# AirPurity.net
KiCad netlist of a schematic drawn in Altium Designer
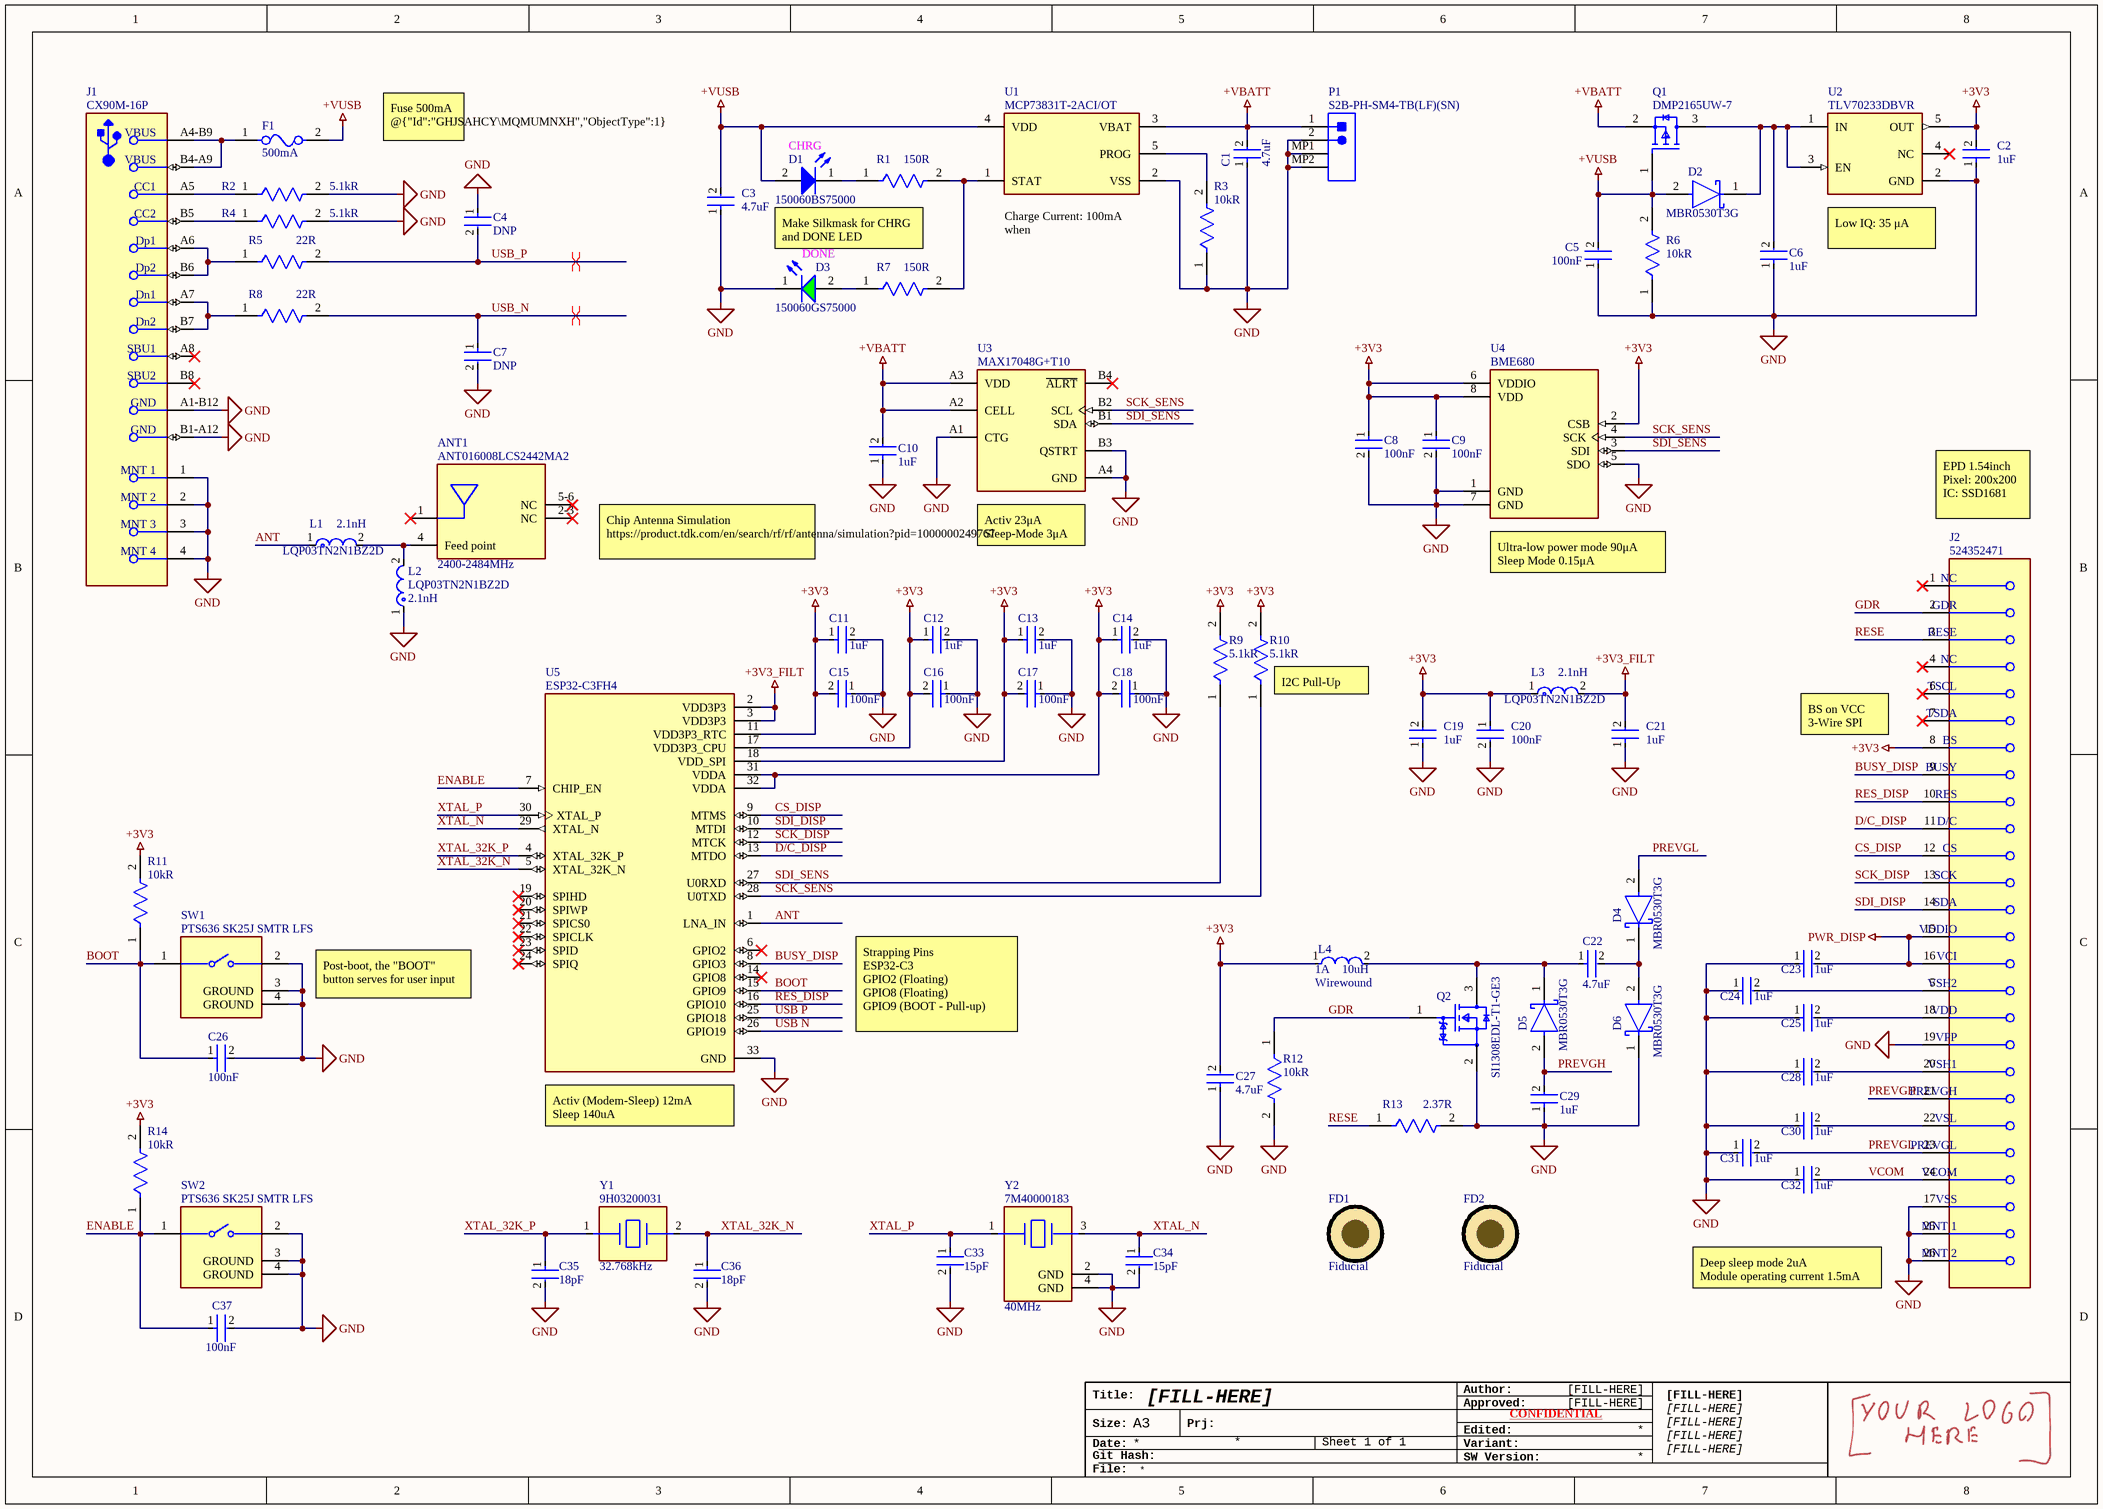
[diagram p0: AirPurity.SchDoc]

(export (version "E")
  (design (tool "Eeschema 10.0.6"))
  (components
    (comp (ref "ANT1")
      (value "ANT016008LCS2442MA2")
      (footprint "FP-ANT016008LCS2442MA2-0")
      (description "RF ANT 2.4GHZ CHIP SOLDER SMD")
      (fields
        (field (name "MANUFACTURER") "TDK Corporation")
        (field (name "OCTOPART") "https://octopart.com/ant016008lcs2442ma2-tdk-48293801")
        (field (name "BANDWIDTH") "2400-2484MHz")
      )
      (libsource (lib "Altium Content Vault") (part "6c2c938d67d116ee9870b08397b3bde"))
    )
    (comp (ref "C1")
      (value "GRM155R61E475ME15D")
      (footprint "FP-GRM155-0_2-MFG")
      (fields (field (name "CAPACITANCE") "4.7uF"))
      (libsource (lib "Altium Content Vault") (part "02cd4be3c70576c341d710602a673aa"))
    )
    (comp (ref "C2")
      (value "GRM155R61E105KA12D")
      (footprint "FP-GRM155-0_1-MFG")
      (description "CERAMIC CAP, MLCC 1UF 50VDC X5R")
      (fields (field (name "CAPACITANCE") "1uF"))
      (libsource (lib "Altium Content Vault") (part "b4654b650e69147ec39a6b967a45e02"))
    )
    (comp (ref "C3")
      (value "GRM155R61E475ME15D")
      (footprint "FP-GRM155-0_2-MFG")
      (fields (field (name "CAPACITANCE") "4.7uF"))
      (libsource (lib "Altium Content Vault") (part "02cd4be3c70576c341d710602a673aa"))
    )
    (comp (ref "C4")
      (value "GRM033R61A104KE15D")
      (footprint "FP-GRM033-0_03-MFG")
      (description "Chip Multilayer Ceramic Capacitors for General Purpose, 0201, 0.10uF, X5R, 15%, 10%, 10V")
      (fields
        (field (name "TOLERANCE") "10%")
        (field (name "CAPACITANCE") "DNP")
        (field (name "VOLTAGE") "10V")
      )
      (libsource (lib "Altium Content Vault") (part "b4654b650e69147ec39a6b967a45e02"))
    )
    (comp (ref "C5")
      (value "GRM033R61A104KE15D")
      (footprint "FP-GRM033-0_03-MFG")
      (description "Chip Multilayer Ceramic Capacitors for General Purpose, 0201, 0.10uF, X5R, 15%, 10%, 10V")
      (fields
        (field (name "TOLERANCE") "10%")
        (field (name "CAPACITANCE") "100nF")
        (field (name "VOLTAGE") "10V")
      )
      (libsource (lib "Altium Content Vault") (part "b4654b650e69147ec39a6b967a45e02"))
    )
    (comp (ref "C6")
      (value "GRM155R61E105KA12D")
      (footprint "FP-GRM155-0_1-MFG")
      (description "CERAMIC CAP, MLCC 1UF 50VDC X5R")
      (fields (field (name "CAPACITANCE") "1uF"))
      (libsource (lib "Altium Content Vault") (part "b4654b650e69147ec39a6b967a45e02"))
    )
    (comp (ref "C7")
      (value "GRM033R61A104KE15D")
      (footprint "FP-GRM033-0_03-MFG")
      (description "Chip Multilayer Ceramic Capacitors for General Purpose, 0201, 0.10uF, X5R, 15%, 10%, 10V")
      (fields
        (field (name "TOLERANCE") "10%")
        (field (name "CAPACITANCE") "DNP")
        (field (name "VOLTAGE") "10V")
      )
      (libsource (lib "Altium Content Vault") (part "b4654b650e69147ec39a6b967a45e02"))
    )
    (comp (ref "C8")
      (value "GRM033R61A104KE15D")
      (footprint "FP-GRM033-0_03-MFG")
      (description "Chip Multilayer Ceramic Capacitors for General Purpose, 0201, 0.10uF, X5R, 15%, 10%, 10V")
      (fields
        (field (name "TOLERANCE") "10%")
        (field (name "CAPACITANCE") "100nF")
        (field (name "VOLTAGE") "10V")
      )
      (libsource (lib "Altium Content Vault") (part "b4654b650e69147ec39a6b967a45e02"))
    )
    (comp (ref "C9")
      (value "GRM033R61A104KE15D")
      (footprint "FP-GRM033-0_03-MFG")
      (description "Chip Multilayer Ceramic Capacitors for General Purpose, 0201, 0.10uF, X5R, 15%, 10%, 10V")
      (fields
        (field (name "TOLERANCE") "10%")
        (field (name "CAPACITANCE") "100nF")
        (field (name "VOLTAGE") "10V")
      )
      (libsource (lib "Altium Content Vault") (part "b4654b650e69147ec39a6b967a45e02"))
    )
    (comp (ref "C10")
      (value "GRM155R61E105KA12D")
      (footprint "FP-GRM155-0_1-MFG")
      (description "CERAMIC CAP, MLCC 1UF 50VDC X5R")
      (fields (field (name "CAPACITANCE") "1uF"))
      (libsource (lib "Altium Content Vault") (part "b4654b650e69147ec39a6b967a45e02"))
    )
    (comp (ref "C11")
      (value "GRM155R61E105KA12D")
      (footprint "FP-GRM155-0_1-MFG")
      (description "CERAMIC CAP, MLCC 1UF 50VDC X5R")
      (fields (field (name "CAPACITANCE") "1uF"))
      (libsource (lib "Altium Content Vault") (part "b4654b650e69147ec39a6b967a45e02"))
    )
    (comp (ref "C12")
      (value "GRM155R61E105KA12D")
      (footprint "FP-GRM155-0_1-MFG")
      (description "CERAMIC CAP, MLCC 1UF 50VDC X5R")
      (fields (field (name "CAPACITANCE") "1uF"))
      (libsource (lib "Altium Content Vault") (part "b4654b650e69147ec39a6b967a45e02"))
    )
    (comp (ref "C13")
      (value "GRM155R61E105KA12D")
      (footprint "FP-GRM155-0_1-MFG")
      (description "CERAMIC CAP, MLCC 1UF 50VDC X5R")
      (fields (field (name "CAPACITANCE") "1uF"))
      (libsource (lib "Altium Content Vault") (part "b4654b650e69147ec39a6b967a45e02"))
    )
    (comp (ref "C14")
      (value "GRM155R61E105KA12D")
      (footprint "FP-GRM155-0_1-MFG")
      (description "CERAMIC CAP, MLCC 1UF 50VDC X5R")
      (fields (field (name "CAPACITANCE") "1uF"))
      (libsource (lib "Altium Content Vault") (part "b4654b650e69147ec39a6b967a45e02"))
    )
    (comp (ref "C15")
      (value "GRM033R61A104KE15D")
      (footprint "FP-GRM033-0_03-MFG")
      (description "Chip Multilayer Ceramic Capacitors for General Purpose, 0201, 0.10uF, X5R, 15%, 10%, 10V")
      (fields
        (field (name "TOLERANCE") "10%")
        (field (name "CAPACITANCE") "100nF")
        (field (name "VOLTAGE") "10V")
      )
      (libsource (lib "Altium Content Vault") (part "b4654b650e69147ec39a6b967a45e02"))
    )
    (comp (ref "C16")
      (value "GRM033R61A104KE15D")
      (footprint "FP-GRM033-0_03-MFG")
      (description "Chip Multilayer Ceramic Capacitors for General Purpose, 0201, 0.10uF, X5R, 15%, 10%, 10V")
      (fields
        (field (name "TOLERANCE") "10%")
        (field (name "CAPACITANCE") "100nF")
        (field (name "VOLTAGE") "10V")
      )
      (libsource (lib "Altium Content Vault") (part "b4654b650e69147ec39a6b967a45e02"))
    )
    (comp (ref "C17")
      (value "GRM033R61A104KE15D")
      (footprint "FP-GRM033-0_03-MFG")
      (description "Chip Multilayer Ceramic Capacitors for General Purpose, 0201, 0.10uF, X5R, 15%, 10%, 10V")
      (fields
        (field (name "TOLERANCE") "10%")
        (field (name "CAPACITANCE") "100nF")
        (field (name "VOLTAGE") "10V")
      )
      (libsource (lib "Altium Content Vault") (part "b4654b650e69147ec39a6b967a45e02"))
    )
    (comp (ref "C18")
      (value "GRM033R61A104KE15D")
      (footprint "FP-GRM033-0_03-MFG")
      (description "Chip Multilayer Ceramic Capacitors for General Purpose, 0201, 0.10uF, X5R, 15%, 10%, 10V")
      (fields
        (field (name "TOLERANCE") "10%")
        (field (name "CAPACITANCE") "100nF")
        (field (name "VOLTAGE") "10V")
      )
      (libsource (lib "Altium Content Vault") (part "b4654b650e69147ec39a6b967a45e02"))
    )
    (comp (ref "C19")
      (value "GRM155R61E105KA12D")
      (footprint "FP-GRM155-0_1-MFG")
      (description "CERAMIC CAP, MLCC 1UF 50VDC X5R")
      (fields (field (name "CAPACITANCE") "1uF"))
      (libsource (lib "Altium Content Vault") (part "b4654b650e69147ec39a6b967a45e02"))
    )
    (comp (ref "C20")
      (value "GRM033R61A104KE15D")
      (footprint "FP-GRM033-0_03-MFG")
      (description "Chip Multilayer Ceramic Capacitors for General Purpose, 0201, 0.10uF, X5R, 15%, 10%, 10V")
      (fields
        (field (name "TOLERANCE") "10%")
        (field (name "CAPACITANCE") "100nF")
        (field (name "VOLTAGE") "10V")
      )
      (libsource (lib "Altium Content Vault") (part "b4654b650e69147ec39a6b967a45e02"))
    )
    (comp (ref "C21")
      (value "GRM155R61E105KA12D")
      (footprint "FP-GRM155-0_1-MFG")
      (description "CERAMIC CAP, MLCC 1UF 50VDC X5R")
      (fields (field (name "CAPACITANCE") "1uF"))
      (libsource (lib "Altium Content Vault") (part "b4654b650e69147ec39a6b967a45e02"))
    )
    (comp (ref "C22")
      (value "GRM155R61E475ME15D")
      (footprint "FP-GRM155-0_2-MFG")
      (fields (field (name "CAPACITANCE") "4.7uF"))
      (libsource (lib "Altium Content Vault") (part "02cd4be3c70576c341d710602a673aa"))
    )
    (comp (ref "C23")
      (value "GRM155R61E105KA12D")
      (footprint "FP-GRM155-0_1-MFG")
      (description "CERAMIC CAP, MLCC 1UF 50VDC X5R")
      (fields (field (name "CAPACITANCE") "1uF"))
      (libsource (lib "Altium Content Vault") (part "b4654b650e69147ec39a6b967a45e02"))
    )
    (comp (ref "C24")
      (value "GRM155R61E105KA12D")
      (footprint "FP-GRM155-0_1-MFG")
      (description "CERAMIC CAP, MLCC 1UF 50VDC X5R")
      (fields (field (name "CAPACITANCE") "1uF"))
      (libsource (lib "Altium Content Vault") (part "b4654b650e69147ec39a6b967a45e02"))
    )
    (comp (ref "C25")
      (value "GRM155R61E105KA12D")
      (footprint "FP-GRM155-0_1-MFG")
      (description "CERAMIC CAP, MLCC 1UF 50VDC X5R")
      (fields (field (name "CAPACITANCE") "1uF"))
      (libsource (lib "Altium Content Vault") (part "b4654b650e69147ec39a6b967a45e02"))
    )
    (comp (ref "C26")
      (value "GRM033R61A104KE15D")
      (footprint "FP-GRM033-0_03-MFG")
      (description "Chip Multilayer Ceramic Capacitors for General Purpose, 0201, 0.10uF, X5R, 15%, 10%, 10V")
      (fields
        (field (name "TOLERANCE") "10%")
        (field (name "CAPACITANCE") "100nF")
        (field (name "VOLTAGE") "10V")
      )
      (libsource (lib "Altium Content Vault") (part "b4654b650e69147ec39a6b967a45e02"))
    )
    (comp (ref "C27")
      (value "GRM155R61E475ME15D")
      (footprint "FP-GRM155-0_2-MFG")
      (fields (field (name "CAPACITANCE") "4.7uF"))
      (libsource (lib "Altium Content Vault") (part "02cd4be3c70576c341d710602a673aa"))
    )
    (comp (ref "C28")
      (value "GRM155R61E105KA12D")
      (footprint "FP-GRM155-0_1-MFG")
      (description "CERAMIC CAP, MLCC 1UF 50VDC X5R")
      (fields (field (name "CAPACITANCE") "1uF"))
      (libsource (lib "Altium Content Vault") (part "b4654b650e69147ec39a6b967a45e02"))
    )
    (comp (ref "C29")
      (value "GRM155R61E105KA12D")
      (footprint "FP-GRM155-0_1-MFG")
      (description "CERAMIC CAP, MLCC 1UF 50VDC X5R")
      (fields (field (name "CAPACITANCE") "1uF"))
      (libsource (lib "Altium Content Vault") (part "b4654b650e69147ec39a6b967a45e02"))
    )
    (comp (ref "C30")
      (value "GRM155R61E105KA12D")
      (footprint "FP-GRM155-0_1-MFG")
      (description "CERAMIC CAP, MLCC 1UF 50VDC X5R")
      (fields (field (name "CAPACITANCE") "1uF"))
      (libsource (lib "Altium Content Vault") (part "b4654b650e69147ec39a6b967a45e02"))
    )
    (comp (ref "C31")
      (value "GRM155R61E105KA12D")
      (footprint "FP-GRM155-0_1-MFG")
      (description "CERAMIC CAP, MLCC 1UF 50VDC X5R")
      (fields (field (name "CAPACITANCE") "1uF"))
      (libsource (lib "Altium Content Vault") (part "b4654b650e69147ec39a6b967a45e02"))
    )
    (comp (ref "C32")
      (value "GRM155R61E105KA12D")
      (footprint "FP-GRM155-0_1-MFG")
      (description "CERAMIC CAP, MLCC 1UF 50VDC X5R")
      (fields (field (name "CAPACITANCE") "1uF"))
      (libsource (lib "Altium Content Vault") (part "b4654b650e69147ec39a6b967a45e02"))
    )
    (comp (ref "C33")
      (value "GRM0335C1H150FA01D")
      (footprint "FP-GRM033-0_03-IPC_B")
      (description "Chip Multilayer Ceramic Capacitors for General Purpose, 0201, 15pF, C0G, 30ppm/°C, 1%, 50V")
      (fields (field (name "CAPACITANCE") "15pF"))
      (libsource (lib "Altium Content Vault") (part "b4654b650e69147ec39a6b967a45e02"))
    )
    (comp (ref "C34")
      (value "GRM0335C1H150FA01D")
      (footprint "FP-GRM033-0_03-IPC_B")
      (description "Chip Multilayer Ceramic Capacitors for General Purpose, 0201, 15pF, C0G, 30ppm/°C, 1%, 50V")
      (fields (field (name "CAPACITANCE") "15pF"))
      (libsource (lib "Altium Content Vault") (part "b4654b650e69147ec39a6b967a45e02"))
    )
    (comp (ref "C35")
      (value "GRM0335C1H180FA01D")
      (footprint "FP-GRM033-0_03-MFG")
      (description "Chip Multilayer Ceramic Capacitors for General Purpose, 0201, 18pF, C0G, 30ppm/°C, 1%, 50V")
      (fields (field (name "CAPACITANCE") "18pF"))
      (libsource (lib "Altium Content Vault") (part "b4654b650e69147ec39a6b967a45e02"))
    )
    (comp (ref "C36")
      (value "GRM0335C1H180FA01D")
      (footprint "FP-GRM033-0_03-MFG")
      (description "Chip Multilayer Ceramic Capacitors for General Purpose, 0201, 18pF, C0G, 30ppm/°C, 1%, 50V")
      (fields (field (name "CAPACITANCE") "18pF"))
      (libsource (lib "Altium Content Vault") (part "b4654b650e69147ec39a6b967a45e02"))
    )
    (comp (ref "C37")
      (value "GRM033R61A104KE15D")
      (footprint "FP-GRM033-0_03-MFG")
      (description "Chip Multilayer Ceramic Capacitors for General Purpose, 0201, 0.10uF, X5R, 15%, 10%, 10V")
      (fields
        (field (name "TOLERANCE") "10%")
        (field (name "CAPACITANCE") "100nF")
        (field (name "VOLTAGE") "10V")
      )
      (libsource (lib "Altium Content Vault") (part "b4654b650e69147ec39a6b967a45e02"))
    )
    (comp (ref "D1")
      (value "150060BS75000")
      (footprint "WL-SMCW_0603_150060xx75000")
      (libsource (lib "Altium Content Vault") (part "LED_Blue_2A-1K"))
    )
    (comp (ref "D2")
      (value "MBR0530T3G")
      (footprint "FP-425-04-MFG")
      (description "DIODE SCHOTTKY 30V 500MA SOD123")
      (libsource (lib "Altium Content Vault") (part "1d6ec82d83fb6aee721767c19dac4b9"))
    )
    (comp (ref "D3")
      (value "150060GS75000")
      (footprint "WL-SMCW_0603_150060xx75000")
      (libsource (lib "Altium Content Vault") (part "LED_Green_2A-1K"))
    )
    (comp (ref "D4")
      (value "MBR0530T3G")
      (footprint "FP-425-04-MFG")
      (description "DIODE SCHOTTKY 30V 500MA SOD123")
      (libsource (lib "Altium Content Vault") (part "1d6ec82d83fb6aee721767c19dac4b9"))
    )
    (comp (ref "D5")
      (value "MBR0530T3G")
      (footprint "FP-425-04-MFG")
      (description "DIODE SCHOTTKY 30V 500MA SOD123")
      (libsource (lib "Altium Content Vault") (part "1d6ec82d83fb6aee721767c19dac4b9"))
    )
    (comp (ref "D6")
      (value "MBR0530T3G")
      (footprint "FP-425-04-MFG")
      (description "DIODE SCHOTTKY 30V 500MA SOD123")
      (libsource (lib "Altium Content Vault") (part "1d6ec82d83fb6aee721767c19dac4b9"))
    )
    (comp (ref "F1")
      (value "0466.500NRHF")
      (footprint "FP-0466-MFG")
      (description "FUSE BOARD MOUNT 500MA 63VAC/VDC")
      (fields (field (name "CURRENT RATING") "500mA"))
      (libsource (lib "Altium Content Vault") (part "5bcf9b9f640e542cf0359d10258e979"))
    )
    (comp (ref "FD1")
      (value "Fiducial")
      (footprint "FIDUCIAL-1MM")
      (libsource (lib "Library") (part "Fiducial"))
    )
    (comp (ref "FD2")
      (value "Fiducial")
      (footprint "FIDUCIAL-1MM")
      (libsource (lib "Library") (part "Fiducial"))
    )
    (comp (ref "J1")
      (value "CX90M-16P")
      (footprint "FP-USB4105-GF-A-MFG")
      (description "CONN RCPT USB2.0 TYPEC 5A")
      (fields (field (name "MANUFACTURER PART NUMBER") "USB4105-GF-A") (field (name "MANUFACTURER") "GCT"))
      (libsource (lib "Library") (part "CMP-245163-000001-1"))
    )
    (comp (ref "J2")
      (value "524352471")
      (footprint "FP-505110-2491-MFG")
      (description "CONN FFC/FPC BOTTOM 24P .5MM R/A")
      (libsource (lib "Library") (part "CMP-04775-000015-1"))
    )
    (comp (ref "L1")
      (value "LQP03TN2N1BZ2D")
      (footprint "FP-LQP03TG_02-IPC_B")
      (description "Film type RF Inductor for Automotive 2.1nH ±0.1nH 600mA 0.15Ω 0201 (0603)")
      (fields (field (name "INDUCTANCE") "2.1nH"))
      (libsource (lib "Altium Content Vault") (part "4cc4b267dca4c8e51f7102f422741d8"))
    )
    (comp (ref "L2")
      (value "LQP03TN2N1BZ2D")
      (footprint "FP-LQP03TG_02-IPC_B")
      (description "Film type RF Inductor for Automotive 2.1nH ±0.1nH 600mA 0.15Ω 0201 (0603)")
      (fields (field (name "INDUCTANCE") "2.1nH"))
      (libsource (lib "Altium Content Vault") (part "4cc4b267dca4c8e51f7102f422741d8"))
    )
    (comp (ref "L3")
      (value "LQP03TN2N1BZ2D")
      (footprint "FP-LQP03TG_02-IPC_B")
      (description "Film type RF Inductor for Automotive 2.1nH ±0.1nH 600mA 0.15Ω 0201 (0603)")
      (fields (field (name "INDUCTANCE") "2.1nH"))
      (libsource (lib "Altium Content Vault") (part "4cc4b267dca4c8e51f7102f422741d8"))
    )
    (comp (ref "L4")
      (value "1239AS-H-100M=P2")
      (footprint "FP-DFE252012C-MFG")
      (description "FIXED IND 10UH 1A 460 MOHM SMD")
      (fields
        (field (name "CURRENT RATING") "1A")
        (field (name "RESISTOR TYPE") "Wirewound")
        (field (name "INDUCTANCE") "10uH")
        (field (name "TOLERANCE") "20%")
      )
      (libsource (lib "Altium Content Vault") (part "725321dda6339637d4d059423bc1c3c"))
    )
    (comp (ref "P1")
      (value "S2B-PH-SM4-TB(LF)(SN)")
      (footprint "JST- S2B-PH-SM4-TB(LF)(SN)-2_V")
      (description "Male Header, Pitch 2 mm, 1 x 2 Position, Height 5.5 mm, -25 to 85 degC, RoHS, Tape and Reel")
      (libsource (lib "Library") (part "CMP-1755-00001-1"))
    )
    (comp (ref "Q1")
      (value "DMP2165UW-7")
      (footprint "FP-SOT323-IPC_B")
      (description "MOSFET BVDSS: 8V-24V SOT323 T&R")
      (libsource (lib "Altium Content Vault") (part "712687b58a63c2867a75c2d2256a34e"))
    )
    (comp (ref "Q2")
      (value "SI1308EDL-T1-GE3")
      (footprint "FP-5549-MFG")
      (description "MOSFET N-CH 30V 1.4A SC-70-3")
      (libsource (lib "Altium Content Vault") (part "e96677422f20f20903245877d22b385"))
    )
    (comp (ref "R1")
      (value "RC0402FR-07150RL")
      (footprint "FP-AC0402-MFG")
      (description "RES 150Ω ±1% 0.063W 0402")
      (fields (field (name "TOLERANCE") "1%") (field (name "RESISTANCE") "150R"))
      (libsource (lib "Altium Content Vault") (part "1029c3af85768c4190bb7ad29bc67b5"))
    )
    (comp (ref "R2")
      (value "RC0402FR-075K1L")
      (footprint "FP-AC0402-MFG")
      (description "RES 5.1kΩ ±1% 0.063W 0402")
      (fields (field (name "RESISTANCE") "5.1kR") (field (name "TOLERANCE") "1%"))
      (libsource (lib "Altium Content Vault") (part "1029c3af85768c4190bb7ad29bc67b5"))
    )
    (comp (ref "R3")
      (value "RC0402FR-0710KL")
      (footprint "FP-AC0402-MFG")
      (description "RES 10kΩ ±1% 0.063W 0402")
      (fields (field (name "TOLERANCE") "1%") (field (name "RESISTANCE") "10kR"))
      (libsource (lib "Altium Content Vault") (part "1029c3af85768c4190bb7ad29bc67b5"))
    )
    (comp (ref "R4")
      (value "RC0402FR-075K1L")
      (footprint "FP-AC0402-MFG")
      (description "RES 5.1kΩ ±1% 0.063W 0402")
      (fields (field (name "RESISTANCE") "5.1kR") (field (name "TOLERANCE") "1%"))
      (libsource (lib "Altium Content Vault") (part "1029c3af85768c4190bb7ad29bc67b5"))
    )
    (comp (ref "R5")
      (value "RC0402FR-0722RL")
      (footprint "FP-AC0402-IPC_A")
      (description "RES 0Ω 0.00% 0.063W 0402")
      (fields (field (name "RESISTANCE") "22R") (field (name "TOLERANCE") "5%"))
      (libsource (lib "Altium Content Vault") (part "1029c3af85768c4190bb7ad29bc67b5"))
    )
    (comp (ref "R6")
      (value "RC0402FR-0710KL")
      (footprint "FP-AC0402-MFG")
      (description "RES 10kΩ ±1% 0.063W 0402")
      (fields (field (name "TOLERANCE") "1%") (field (name "RESISTANCE") "10kR"))
      (libsource (lib "Altium Content Vault") (part "1029c3af85768c4190bb7ad29bc67b5"))
    )
    (comp (ref "R7")
      (value "RC0402FR-07150RL")
      (footprint "FP-AC0402-MFG")
      (description "RES 150Ω ±1% 0.063W 0402")
      (fields (field (name "TOLERANCE") "1%") (field (name "RESISTANCE") "150R"))
      (libsource (lib "Altium Content Vault") (part "1029c3af85768c4190bb7ad29bc67b5"))
    )
    (comp (ref "R8")
      (value "RC0402FR-0722RL")
      (footprint "FP-AC0402-IPC_A")
      (description "RES 0Ω 0.00% 0.063W 0402")
      (fields (field (name "RESISTANCE") "22R") (field (name "TOLERANCE") "5%"))
      (libsource (lib "Altium Content Vault") (part "1029c3af85768c4190bb7ad29bc67b5"))
    )
    (comp (ref "R9")
      (value "RC0402FR-075K1L")
      (footprint "FP-AC0402-MFG")
      (description "RES 5.1kΩ ±1% 0.063W 0402")
      (fields (field (name "RESISTANCE") "5.1kR") (field (name "TOLERANCE") "1%"))
      (libsource (lib "Altium Content Vault") (part "1029c3af85768c4190bb7ad29bc67b5"))
    )
    (comp (ref "R10")
      (value "RC0402FR-075K1L")
      (footprint "FP-AC0402-MFG")
      (description "RES 5.1kΩ ±1% 0.063W 0402")
      (fields (field (name "RESISTANCE") "5.1kR") (field (name "TOLERANCE") "1%"))
      (libsource (lib "Altium Content Vault") (part "1029c3af85768c4190bb7ad29bc67b5"))
    )
    (comp (ref "R11")
      (value "RC0402FR-0710KL")
      (footprint "FP-AC0402-MFG")
      (description "RES 10kΩ ±1% 0.063W 0402")
      (fields (field (name "TOLERANCE") "1%") (field (name "RESISTANCE") "10kR"))
      (libsource (lib "Altium Content Vault") (part "1029c3af85768c4190bb7ad29bc67b5"))
    )
    (comp (ref "R12")
      (value "RC0402FR-0710KL")
      (footprint "FP-AC0402-MFG")
      (description "RES 10kΩ ±1% 0.063W 0402")
      (fields (field (name "TOLERANCE") "1%") (field (name "RESISTANCE") "10kR"))
      (libsource (lib "Altium Content Vault") (part "1029c3af85768c4190bb7ad29bc67b5"))
    )
    (comp (ref "R13")
      (value "RC0402FR-072R37L")
      (footprint "FP-AC0402-IPC_A")
      (description "RES 3Ω ±1% 0.063W 0402")
      (fields (field (name "TOLERANCE") "1%") (field (name "RESISTANCE") "2.37R"))
      (libsource (lib "Altium Content Vault") (part "1029c3af85768c4190bb7ad29bc67b5"))
    )
    (comp (ref "R14")
      (value "RC0402FR-0710KL")
      (footprint "FP-AC0402-MFG")
      (description "RES 10kΩ ±1% 0.063W 0402")
      (fields (field (name "TOLERANCE") "1%") (field (name "RESISTANCE") "10kR"))
      (libsource (lib "Altium Content Vault") (part "1029c3af85768c4190bb7ad29bc67b5"))
    )
    (comp (ref "SW1")
      (value "PTS636 SK25J SMTR LFS")
      (footprint "FP-PTS636_SKG25_SMTR_LFS-MFG")
      (description "TACT 6.0 X 3.5, 2.5 MM H, 250GF,")
      (libsource (lib "Altium Content Vault") (part "bdfe703aeb3461bf7c331fe9d798369"))
    )
    (comp (ref "SW2")
      (value "PTS636 SK25J SMTR LFS")
      (footprint "FP-PTS636_SKG25_SMTR_LFS-MFG")
      (description "TACT 6.0 X 3.5, 2.5 MM H, 250GF,")
      (libsource (lib "Altium Content Vault") (part "bdfe703aeb3461bf7c331fe9d798369"))
    )
    (comp (ref "U1")
      (value "MCP73831T-2ACI/OT")
      (footprint "FP-SOT23-5LD-PL-1-MFG")
      (description "IC CONTROLLR LI-ION 4.2V SOT23-5")
      (libsource (lib "Library") (part "CMP-0133-00143-2"))
    )
    (comp (ref "U2")
      (value "TLV70233DBVR")
      (footprint "FP-DBV0005A-MFG")
      (description "None")
      (libsource (lib "Altium Content Vault") (part "420f3d6e5f30de690793e198760af83"))
    )
    (comp (ref "U3")
      (value "MAX17048G+T10")
      (footprint "FP-W80B1-1-MFG")
      (description "IC FUEL GAUGE LI-ION 1CELL 8WLP")
      (fields
        (field (name "OCTOPART") "https://octopart.com/max17048x%2Bt10-maxim+integrated-20327623")
        (field (name "MANUFACTURER") "Maxim")
      )
      (libsource (lib "Altium Content Vault") (part "bcaa5b8bc81e7d514695bf68e689a73"))
    )
    (comp (ref "U4")
      (value "BME680")
      (footprint "PSON80P300X300X100-8N")
      (description "Gas, Humidity, Pressure, Temperature Sensor IÂ²C, SPI Output")
      (fields (field (name "MF") "Bosch Sensortec"))
      (libsource (lib "Library") (part "BME680"))
    )
    (comp (ref "U5")
      (value "ESP32-C3FH4")
      (footprint "QFN50P500X500X90-33N")
      (fields (field (name "MF") "Espressif Systems"))
      (libsource (lib "Library") (part "ESP32-C3FH4"))
    )
    (comp (ref "Y1")
      (value "9H03200031")
      (footprint "FP-ABS07AIG-MFG")
      (description "Crystal 32.768kHz ±20ppm (Tol) 7pF FUND 70kΩ Automotive 2-Pin Mini-CSMD T/R")
      (fields (field (name "FREQUENCY") "32.768kHz"))
      (libsource (lib "Library") (part "CMP-27762-015608-1"))
    )
    (comp (ref "Y2")
      (value "7M40000183")
      (footprint "FP-ABM11-MFG")
      (description "Crystal 40MHz ±10ppm 10pF SMD-4 2mm x 1.6mm")
      (fields (field (name "FREQUENCY") "40MHz"))
      (libsource (lib "Altium Content Vault") (part "b3c1237d77310e73098bcf11eecb25f"))
    )
  )
  (nets
    (net (code "1") (name "+3V3") (class "Default")
      (node (ref "C11") (pin "1") (pinfunction "1_1") (pintype "passive"))
      (node (ref "C12") (pin "1") (pinfunction "1_1") (pintype "passive"))
      (node (ref "C13") (pin "1") (pinfunction "1_1") (pintype "passive"))
      (node (ref "C14") (pin "1") (pinfunction "1_1") (pintype "passive"))
      (node (ref "C15") (pin "2") (pinfunction "2_2") (pintype "passive"))
      (node (ref "C16") (pin "2") (pinfunction "2_2") (pintype "passive"))
      (node (ref "C17") (pin "2") (pinfunction "2_2") (pintype "passive"))
      (node (ref "C18") (pin "2") (pinfunction "2_2") (pintype "passive"))
      (node (ref "C19") (pin "2") (pinfunction "2_2") (pintype "passive"))
      (node (ref "C2") (pin "2") (pinfunction "2_2") (pintype "passive"))
      (node (ref "C20") (pin "1") (pinfunction "1_1") (pintype "passive"))
      (node (ref "C27") (pin "2") (pinfunction "2_2") (pintype "passive"))
      (node (ref "C8") (pin "1") (pinfunction "1_1") (pintype "passive"))
      (node (ref "C9") (pin "1") (pinfunction "1_1") (pintype "passive"))
      (node (ref "J2") (pin "8") (pinfunction "8_8") (pintype "passive"))
      (node (ref "L3") (pin "1") (pinfunction "1_1") (pintype "passive"))
      (node (ref "L4") (pin "1") (pinfunction "1_1") (pintype "passive"))
      (node (ref "R10") (pin "2") (pinfunction "2_2") (pintype "passive"))
      (node (ref "R11") (pin "2") (pinfunction "2_2") (pintype "passive"))
      (node (ref "R14") (pin "2") (pinfunction "2_2") (pintype "passive"))
      (node (ref "R9") (pin "2") (pinfunction "2_2") (pintype "passive"))
      (node (ref "U2") (pin "5") (pinfunction "OUT_5") (pintype "output"))
      (node (ref "U4") (pin "2") (pinfunction "CSB_2") (pintype "input"))
      (node (ref "U4") (pin "6") (pinfunction "VDDIO_6") (pintype "power_in"))
      (node (ref "U4") (pin "8") (pinfunction "VDD_8") (pintype "power_in"))
      (node (ref "U5") (pin "11") (pinfunction "VDD3P3_RTC_11") (pintype "power_in"))
      (node (ref "U5") (pin "17") (pinfunction "VDD3P3_CPU_17") (pintype "power_in"))
      (node (ref "U5") (pin "18") (pinfunction "VDD_SPI_18") (pintype "power_in"))
      (node (ref "U5") (pin "31") (pinfunction "VDDA_31") (pintype "power_in"))
      (node (ref "U5") (pin "32") (pinfunction "VDDA_32") (pintype "power_in"))
    )
    (net (code "2") (name "+3V3_FILT") (class "Default")
      (node (ref "C21") (pin "2") (pinfunction "2_2") (pintype "passive"))
      (node (ref "L3") (pin "2") (pinfunction "2_2") (pintype "passive"))
      (node (ref "U5") (pin "2") (pinfunction "VDD3P3_2") (pintype "power_in"))
      (node (ref "U5") (pin "3") (pinfunction "VDD3P3_3") (pintype "power_in"))
    )
    (net (code "3") (name "+VBATT") (class "Default")
      (node (ref "C1") (pin "2") (pinfunction "2_2") (pintype "passive"))
      (node (ref "C10") (pin "2") (pinfunction "2_2") (pintype "passive"))
      (node (ref "P1") (pin "1") (pinfunction "1_1") (pintype "passive"))
      (node (ref "Q1") (pin "2") (pinfunction "S_2") (pintype "passive"))
      (node (ref "U1") (pin "3") (pinfunction "VBAT_3") (pintype "power_in"))
      (node (ref "U3") (pin "A2") (pinfunction "CELL_A2") (pintype "power_in"))
      (node (ref "U3") (pin "A3") (pinfunction "VDD_A3") (pintype "power_in"))
    )
    (net (code "4") (name "+VUSB") (class "Default")
      (node (ref "C3") (pin "2") (pinfunction "2_2") (pintype "passive"))
      (node (ref "C5") (pin "2") (pinfunction "2_2") (pintype "passive"))
      (node (ref "D1") (pin "2") (pinfunction "A_2") (pintype "passive"))
      (node (ref "D2") (pin "2") (pinfunction "A_2") (pintype "passive"))
      (node (ref "F1") (pin "2") (pinfunction "2_2") (pintype "passive"))
      (node (ref "Q1") (pin "1") (pinfunction "G_1") (pintype "passive"))
      (node (ref "R6") (pin "2") (pinfunction "2_2") (pintype "passive"))
      (node (ref "U1") (pin "4") (pinfunction "VDD_4") (pintype "power_in"))
    )
    (net (code "5") (name "/ANT") (class "Default")
      (node (ref "L1") (pin "1") (pinfunction "1_1") (pintype "passive"))
      (node (ref "U5") (pin "1") (pinfunction "LNA_IN_1") (pintype "bidirectional"))
    )
    (net (code "6") (name "/BOOT") (class "Default")
      (node (ref "C26") (pin "1") (pinfunction "1_1") (pintype "passive"))
      (node (ref "R11") (pin "1") (pinfunction "1_1") (pintype "passive"))
      (node (ref "SW1") (pin "1") (pinfunction "1_1") (pintype "passive"))
      (node (ref "U5") (pin "15") (pinfunction "GPIO9_15") (pintype "bidirectional"))
    )
    (net (code "7") (name "/BUSY_DISP") (class "Default")
      (node (ref "J2") (pin "9") (pinfunction "9_9") (pintype "passive"))
      (node (ref "U5") (pin "8") (pinfunction "GPIO3_8") (pintype "bidirectional"))
    )
    (net (code "8") (name "/CS_DISP") (class "Default")
      (node (ref "J2") (pin "12") (pinfunction "12_12") (pintype "passive"))
      (node (ref "U5") (pin "9") (pinfunction "MTMS_9") (pintype "bidirectional"))
    )
    (net (code "9") (name "/D{slash}C_DISP") (class "Default")
      (node (ref "J2") (pin "11") (pinfunction "11_11") (pintype "passive"))
      (node (ref "U5") (pin "13") (pinfunction "MTDO_13") (pintype "bidirectional"))
    )
    (net (code "10") (name "/ENABLE") (class "Default")
      (node (ref "C37") (pin "1") (pinfunction "1_1") (pintype "passive"))
      (node (ref "R14") (pin "1") (pinfunction "1_1") (pintype "passive"))
      (node (ref "SW2") (pin "1") (pinfunction "1_1") (pintype "passive"))
      (node (ref "U5") (pin "7") (pinfunction "CHIP_EN_7") (pintype "input"))
    )
    (net (code "11") (name "/GDR") (class "Default")
      (node (ref "J2") (pin "2") (pinfunction "2_2") (pintype "passive"))
      (node (ref "Q2") (pin "1") (pinfunction "G_1") (pintype "passive"))
      (node (ref "R12") (pin "1") (pinfunction "1_1") (pintype "passive"))
    )
    (net (code "12") (name "/PREVGH") (class "Default")
      (node (ref "C29") (pin "2") (pinfunction "2_2") (pintype "passive"))
      (node (ref "D5") (pin "2") (pinfunction "A_2") (pintype "passive"))
      (node (ref "J2") (pin "21") (pinfunction "21_21") (pintype "passive"))
    )
    (net (code "13") (name "/PREVGL") (class "Default")
      (node (ref "C31") (pin "2") (pinfunction "2_2") (pintype "passive"))
      (node (ref "D4") (pin "2") (pinfunction "A_2") (pintype "passive"))
      (node (ref "J2") (pin "23") (pinfunction "23_23") (pintype "passive"))
    )
    (net (code "14") (name "/RESE") (class "Default")
      (node (ref "J2") (pin "3") (pinfunction "3_3") (pintype "passive"))
      (node (ref "R13") (pin "1") (pinfunction "1_1") (pintype "passive"))
    )
    (net (code "15") (name "/RES_DISP") (class "Default")
      (node (ref "J2") (pin "10") (pinfunction "10_10") (pintype "passive"))
      (node (ref "U5") (pin "16") (pinfunction "GPIO10_16") (pintype "bidirectional"))
    )
    (net (code "16") (name "/SCK_DISP") (class "Default")
      (node (ref "J2") (pin "13") (pinfunction "13_13") (pintype "passive"))
      (node (ref "U5") (pin "12") (pinfunction "MTCK_12") (pintype "bidirectional"))
    )
    (net (code "17") (name "/SCK_SENS") (class "Default")
      (node (ref "R10") (pin "1") (pinfunction "1_1") (pintype "passive"))
      (node (ref "U3") (pin "B2") (pinfunction "SCL_B2") (pintype "input"))
      (node (ref "U4") (pin "4") (pinfunction "SCK_4") (pintype "input"))
      (node (ref "U5") (pin "28") (pinfunction "U0TXD_28") (pintype "bidirectional"))
    )
    (net (code "18") (name "/SDI_DISP") (class "Default")
      (node (ref "J2") (pin "14") (pinfunction "14_14") (pintype "passive"))
      (node (ref "U5") (pin "10") (pinfunction "MTDI_10") (pintype "bidirectional"))
    )
    (net (code "19") (name "/SDI_SENS") (class "Default")
      (node (ref "R9") (pin "1") (pinfunction "1_1") (pintype "passive"))
      (node (ref "U3") (pin "B1") (pinfunction "SDA_B1") (pintype "bidirectional"))
      (node (ref "U4") (pin "3") (pinfunction "SDI_3") (pintype "bidirectional"))
      (node (ref "U5") (pin "27") (pinfunction "U0RXD_27") (pintype "bidirectional"))
    )
    (net (code "20") (name "/USB N") (class "Default")
      (node (ref "U5") (pin "26") (pinfunction "GPIO19_26") (pintype "bidirectional"))
    )
    (net (code "21") (name "/USB P") (class "Default")
      (node (ref "U5") (pin "25") (pinfunction "GPIO18_25") (pintype "bidirectional"))
    )
    (net (code "22") (name "/USB_N") (class "Default")
      (node (ref "C7") (pin "1") (pinfunction "1_1") (pintype "passive"))
      (node (ref "R8") (pin "2") (pinfunction "2_2") (pintype "passive"))
    )
    (net (code "23") (name "/USB_P") (class "Default")
      (node (ref "C4") (pin "2") (pinfunction "2_2") (pintype "passive"))
      (node (ref "R5") (pin "2") (pinfunction "2_2") (pintype "passive"))
    )
    (net (code "24") (name "/VCOM") (class "Default")
      (node (ref "C32") (pin "2") (pinfunction "2_2") (pintype "passive"))
      (node (ref "J2") (pin "24") (pinfunction "24_24") (pintype "passive"))
    )
    (net (code "25") (name "/XTAL_32K_N") (class "Default")
      (node (ref "C36") (pin "1") (pinfunction "1_1") (pintype "passive"))
      (node (ref "U5") (pin "5") (pinfunction "XTAL_32K_N_5") (pintype "bidirectional"))
      (node (ref "Y1") (pin "2") (pinfunction "2_2") (pintype "passive"))
    )
    (net (code "26") (name "/XTAL_32K_P") (class "Default")
      (node (ref "C35") (pin "1") (pinfunction "1_1") (pintype "passive"))
      (node (ref "U5") (pin "4") (pinfunction "XTAL_32K_P_4") (pintype "bidirectional"))
      (node (ref "Y1") (pin "1") (pinfunction "1_1") (pintype "passive"))
    )
    (net (code "27") (name "/XTAL_N") (class "Default")
      (node (ref "C34") (pin "1") (pinfunction "1_1") (pintype "passive"))
      (node (ref "U5") (pin "29") (pinfunction "XTAL_N_29") (pintype "output"))
      (node (ref "Y2") (pin "3") (pinfunction "3_3") (pintype "passive"))
    )
    (net (code "28") (name "/XTAL_P") (class "Default")
      (node (ref "C33") (pin "1") (pinfunction "1_1") (pintype "passive"))
      (node (ref "U5") (pin "30") (pinfunction "XTAL_P_30") (pintype "input"))
      (node (ref "Y2") (pin "1") (pinfunction "1_1") (pintype "passive"))
    )
    (net (code "29") (name "GND") (class "Default")
      (node (ref "C1") (pin "1") (pinfunction "1_1") (pintype "passive"))
      (node (ref "C10") (pin "1") (pinfunction "1_1") (pintype "passive"))
      (node (ref "C11") (pin "2") (pinfunction "2_2") (pintype "passive"))
      (node (ref "C12") (pin "2") (pinfunction "2_2") (pintype "passive"))
      (node (ref "C13") (pin "2") (pinfunction "2_2") (pintype "passive"))
      (node (ref "C14") (pin "2") (pinfunction "2_2") (pintype "passive"))
      (node (ref "C15") (pin "1") (pinfunction "1_1") (pintype "passive"))
      (node (ref "C16") (pin "1") (pinfunction "1_1") (pintype "passive"))
      (node (ref "C17") (pin "1") (pinfunction "1_1") (pintype "passive"))
      (node (ref "C18") (pin "1") (pinfunction "1_1") (pintype "passive"))
      (node (ref "C19") (pin "1") (pinfunction "1_1") (pintype "passive"))
      (node (ref "C2") (pin "1") (pinfunction "1_1") (pintype "passive"))
      (node (ref "C20") (pin "2") (pinfunction "2_2") (pintype "passive"))
      (node (ref "C21") (pin "1") (pinfunction "1_1") (pintype "passive"))
      (node (ref "C23") (pin "1") (pinfunction "1_1") (pintype "passive"))
      (node (ref "C24") (pin "1") (pinfunction "1_1") (pintype "passive"))
      (node (ref "C25") (pin "1") (pinfunction "1_1") (pintype "passive"))
      (node (ref "C26") (pin "2") (pinfunction "2_2") (pintype "passive"))
      (node (ref "C27") (pin "1") (pinfunction "1_1") (pintype "passive"))
      (node (ref "C28") (pin "1") (pinfunction "1_1") (pintype "passive"))
      (node (ref "C29") (pin "1") (pinfunction "1_1") (pintype "passive"))
      (node (ref "C3") (pin "1") (pinfunction "1_1") (pintype "passive"))
      (node (ref "C30") (pin "1") (pinfunction "1_1") (pintype "passive"))
      (node (ref "C31") (pin "1") (pinfunction "1_1") (pintype "passive"))
      (node (ref "C32") (pin "1") (pinfunction "1_1") (pintype "passive"))
      (node (ref "C33") (pin "2") (pinfunction "2_2") (pintype "passive"))
      (node (ref "C34") (pin "2") (pinfunction "2_2") (pintype "passive"))
      (node (ref "C35") (pin "2") (pinfunction "2_2") (pintype "passive"))
      (node (ref "C36") (pin "2") (pinfunction "2_2") (pintype "passive"))
      (node (ref "C37") (pin "2") (pinfunction "2_2") (pintype "passive"))
      (node (ref "C4") (pin "1") (pinfunction "1_1") (pintype "passive"))
      (node (ref "C5") (pin "1") (pinfunction "1_1") (pintype "passive"))
      (node (ref "C6") (pin "1") (pinfunction "1_1") (pintype "passive"))
      (node (ref "C7") (pin "2") (pinfunction "2_2") (pintype "passive"))
      (node (ref "C8") (pin "2") (pinfunction "2_2") (pintype "passive"))
      (node (ref "C9") (pin "2") (pinfunction "2_2") (pintype "passive"))
      (node (ref "D3") (pin "1") (pinfunction "K_1") (pintype "passive"))
      (node (ref "D6") (pin "1") (pinfunction "C_1") (pintype "passive"))
      (node (ref "J1") (pin "1") (pinfunction "MNT_1_1") (pintype "power_in"))
      (node (ref "J1") (pin "2") (pinfunction "MNT_2_2") (pintype "power_in"))
      (node (ref "J1") (pin "3") (pinfunction "MNT_3_3") (pintype "power_in"))
      (node (ref "J1") (pin "4") (pinfunction "MNT_4_4") (pintype "power_in"))
      (node (ref "J1") (pin "A1-B12") (pinfunction "GND_A1-B12") (pintype "power_in"))
      (node (ref "J1") (pin "B1-A12") (pinfunction "GND_B1-A12") (pintype "bidirectional"))
      (node (ref "J2") (pin "17") (pinfunction "17_17") (pintype "passive"))
      (node (ref "J2") (pin "19") (pinfunction "19_19") (pintype "passive"))
      (node (ref "J2") (pin "25") (pinfunction "MNT_1_25") (pintype "passive"))
      (node (ref "J2") (pin "26") (pinfunction "MNT_2_26") (pintype "passive"))
      (node (ref "L2") (pin "1") (pinfunction "1_1") (pintype "passive"))
      (node (ref "P1") (pin "2") (pinfunction "2_2") (pintype "passive"))
      (node (ref "P1") (pin "MP1") (pinfunction "MP1_MP1") (pintype "passive"))
      (node (ref "P1") (pin "MP2") (pinfunction "MP2_MP2") (pintype "passive"))
      (node (ref "Q2") (pin "2") (pinfunction "S_2") (pintype "passive"))
      (node (ref "R12") (pin "2") (pinfunction "2_2") (pintype "passive"))
      (node (ref "R13") (pin "2") (pinfunction "2_2") (pintype "passive"))
      (node (ref "R2") (pin "2") (pinfunction "2_2") (pintype "passive"))
      (node (ref "R3") (pin "1") (pinfunction "1_1") (pintype "passive"))
      (node (ref "R4") (pin "2") (pinfunction "2_2") (pintype "passive"))
      (node (ref "R6") (pin "1") (pinfunction "1_1") (pintype "passive"))
      (node (ref "SW1") (pin "2") (pinfunction "2_2") (pintype "passive"))
      (node (ref "SW1") (pin "3") (pinfunction "GROUND_3") (pintype "power_in"))
      (node (ref "SW1") (pin "4") (pinfunction "GROUND_4") (pintype "power_in"))
      (node (ref "SW2") (pin "2") (pinfunction "2_2") (pintype "passive"))
      (node (ref "SW2") (pin "3") (pinfunction "GROUND_3") (pintype "power_in"))
      (node (ref "SW2") (pin "4") (pinfunction "GROUND_4") (pintype "power_in"))
      (node (ref "U1") (pin "2") (pinfunction "VSS_2") (pintype "power_in"))
      (node (ref "U2") (pin "2") (pinfunction "GND_2") (pintype "power_in"))
      (node (ref "U3") (pin "A1") (pinfunction "CTG_A1") (pintype "power_in"))
      (node (ref "U3") (pin "A4") (pinfunction "GND_A4") (pintype "power_in"))
      (node (ref "U3") (pin "B3") (pinfunction "QSTRT_B3") (pintype "power_in"))
      (node (ref "U4") (pin "1") (pinfunction "GND_1") (pintype "power_in"))
      (node (ref "U4") (pin "5") (pinfunction "SDO_5") (pintype "bidirectional"))
      (node (ref "U4") (pin "7") (pinfunction "GND_7") (pintype "power_in"))
      (node (ref "U5") (pin "33") (pinfunction "GND_33") (pintype "power_in"))
      (node (ref "Y2") (pin "2") (pinfunction "GND_2") (pintype "power_in"))
      (node (ref "Y2") (pin "4") (pinfunction "GND_4") (pintype "power_in"))
    )
    (net (code "30") (name "Net-(ANT1-Feed_point)") (class "Default")
      (node (ref "ANT1") (pin "4") (pinfunction "Feed_point_4") (pintype "passive"))
      (node (ref "L1") (pin "2") (pinfunction "2_2") (pintype "passive"))
      (node (ref "L2") (pin "2") (pinfunction "2_2") (pintype "passive"))
    )
    (net (code "31") (name "Net-(C24-Pad2)") (class "Default")
      (node (ref "C24") (pin "2") (pinfunction "2_2") (pintype "passive"))
      (node (ref "J2") (pin "5") (pinfunction "5_5") (pintype "passive"))
    )
    (net (code "32") (name "Net-(C25-Pad2)") (class "Default")
      (node (ref "C25") (pin "2") (pinfunction "2_2") (pintype "passive"))
      (node (ref "J2") (pin "18") (pinfunction "18_18") (pintype "passive"))
    )
    (net (code "33") (name "Net-(C28-Pad2)") (class "Default")
      (node (ref "C28") (pin "2") (pinfunction "2_2") (pintype "passive"))
      (node (ref "J2") (pin "20") (pinfunction "20_20") (pintype "passive"))
    )
    (net (code "34") (name "Net-(C30-Pad2)") (class "Default")
      (node (ref "C30") (pin "2") (pinfunction "2_2") (pintype "passive"))
      (node (ref "J2") (pin "22") (pinfunction "22_22") (pintype "passive"))
    )
    (net (code "35") (name "Net-(D1-K)") (class "Default")
      (node (ref "D1") (pin "1") (pinfunction "K_1") (pintype "passive"))
      (node (ref "R1") (pin "1") (pinfunction "1_1") (pintype "passive"))
    )
    (net (code "36") (name "Net-(D2-C)") (class "Default")
      (node (ref "C6") (pin "2") (pinfunction "2_2") (pintype "passive"))
      (node (ref "D2") (pin "1") (pinfunction "C_1") (pintype "passive"))
      (node (ref "Q1") (pin "3") (pinfunction "D_3") (pintype "passive"))
      (node (ref "U2") (pin "1") (pinfunction "IN_1") (pintype "power_in"))
      (node (ref "U2") (pin "3") (pinfunction "EN_3") (pintype "input"))
    )
    (net (code "37") (name "Net-(D3-A)") (class "Default")
      (node (ref "D3") (pin "2") (pinfunction "A_2") (pintype "passive"))
      (node (ref "R7") (pin "1") (pinfunction "1_1") (pintype "passive"))
    )
    (net (code "38") (name "Net-(D4-C)") (class "Default")
      (node (ref "C22") (pin "2") (pinfunction "2_2") (pintype "passive"))
      (node (ref "D4") (pin "1") (pinfunction "C_1") (pintype "passive"))
      (node (ref "D6") (pin "2") (pinfunction "A_2") (pintype "passive"))
    )
    (net (code "39") (name "Net-(D5-C)") (class "Default")
      (node (ref "C22") (pin "1") (pinfunction "1_1") (pintype "passive"))
      (node (ref "D5") (pin "1") (pinfunction "C_1") (pintype "passive"))
      (node (ref "L4") (pin "2") (pinfunction "2_2") (pintype "passive"))
      (node (ref "Q2") (pin "3") (pinfunction "D_3") (pintype "passive"))
    )
    (net (code "40") (name "Net-(F1-Pad1)") (class "Default")
      (node (ref "F1") (pin "1") (pinfunction "1_1") (pintype "passive"))
      (node (ref "J1") (pin "A4-B9") (pinfunction "VBUS_A4-B9") (pintype "power_in"))
      (node (ref "J1") (pin "B4-A9") (pinfunction "VBUS_B4-A9") (pintype "bidirectional"))
    )
    (net (code "41") (name "Net-(J1-CC1)") (class "Default")
      (node (ref "J1") (pin "A5") (pinfunction "CC1_A5") (pintype "power_in"))
      (node (ref "R2") (pin "1") (pinfunction "1_1") (pintype "passive"))
    )
    (net (code "42") (name "Net-(J1-CC2)") (class "Default")
      (node (ref "J1") (pin "B5") (pinfunction "CC2_B5") (pintype "bidirectional"))
      (node (ref "R4") (pin "1") (pinfunction "1_1") (pintype "passive"))
    )
    (net (code "43") (name "Net-(J1-Dn1)") (class "Default")
      (node (ref "J1") (pin "A7") (pinfunction "Dn1_A7") (pintype "bidirectional"))
      (node (ref "J1") (pin "B7") (pinfunction "Dn2_B7") (pintype "bidirectional"))
      (node (ref "R8") (pin "1") (pinfunction "1_1") (pintype "passive"))
    )
    (net (code "44") (name "Net-(J1-Dp1)") (class "Default")
      (node (ref "J1") (pin "A6") (pinfunction "Dp1_A6") (pintype "bidirectional"))
      (node (ref "J1") (pin "B6") (pinfunction "Dp2_B6") (pintype "bidirectional"))
      (node (ref "R5") (pin "1") (pinfunction "1_1") (pintype "passive"))
    )
    (net (code "45") (name "Net-(U1-PROG)") (class "Default")
      (node (ref "R3") (pin "2") (pinfunction "2_2") (pintype "passive"))
      (node (ref "U1") (pin "5") (pinfunction "PROG_5") (pintype "passive"))
    )
    (net (code "46") (name "Net-(U1-STAT)") (class "Default")
      (node (ref "R1") (pin "2") (pinfunction "2_2") (pintype "passive"))
      (node (ref "R7") (pin "2") (pinfunction "2_2") (pintype "passive"))
      (node (ref "U1") (pin "1") (pinfunction "STAT_1") (pintype "passive"))
    )
    (net (code "47") (name "PWR_DISP") (class "Default")
      (node (ref "C23") (pin "2") (pinfunction "2_2") (pintype "passive"))
      (node (ref "J2") (pin "15") (pinfunction "15_15") (pintype "passive"))
      (node (ref "J2") (pin "16") (pinfunction "16_16") (pintype "passive"))
    )
    (net (code "48") (name "unconnected-(ANT1-NC-Pad2-3)") (class "Default")
      (node (ref "ANT1") (pin "2-3") (pinfunction "NC_2-3") (pintype "passive+no_connect"))
    )
    (net (code "49") (name "unconnected-(ANT1-NC-Pad5-6)") (class "Default")
      (node (ref "ANT1") (pin "5-6") (pinfunction "NC_5-6") (pintype "passive+no_connect"))
    )
    (net (code "50") (name "unconnected-(ANT1-Radiator_electrode-Pad1)") (class "Default")
      (node (ref "ANT1") (pin "1") (pinfunction "Radiator_electrode_1") (pintype "passive+no_connect"))
    )
    (net (code "51") (name "unconnected-(J1-SBU1-PadA8)") (class "Default")
      (node (ref "J1") (pin "A8") (pinfunction "SBU1_A8") (pintype "bidirectional+no_connect"))
    )
    (net (code "52") (name "unconnected-(J1-SBU2-PadB8)") (class "Default")
      (node (ref "J1") (pin "B8") (pinfunction "SBU2_B8") (pintype "power_in+no_connect"))
    )
    (net (code "53") (name "unconnected-(J2-Pad1)") (class "Default")
      (node (ref "J2") (pin "1") (pinfunction "1_1") (pintype "passive+no_connect"))
    )
    (net (code "54") (name "unconnected-(J2-Pad4)") (class "Default")
      (node (ref "J2") (pin "4") (pinfunction "4_4") (pintype "passive+no_connect"))
    )
    (net (code "55") (name "unconnected-(J2-Pad6)") (class "Default")
      (node (ref "J2") (pin "6") (pinfunction "6_6") (pintype "passive+no_connect"))
    )
    (net (code "56") (name "unconnected-(J2-Pad7)") (class "Default")
      (node (ref "J2") (pin "7") (pinfunction "7_7") (pintype "passive+no_connect"))
    )
    (net (code "57") (name "unconnected-(U2-NC-Pad4)") (class "Default")
      (node (ref "U2") (pin "4") (pinfunction "NC_4") (pintype "passive+no_connect"))
    )
    (net (code "58") (name "unconnected-(U3-~{ALRT}-PadB4)") (class "Default")
      (node (ref "U3") (pin "B4") (pinfunction "~{ALRT}_B4") (pintype "open_collector+no_connect"))
    )
    (net (code "59") (name "unconnected-(U5-GPIO2-Pad6)") (class "Default")
      (node (ref "U5") (pin "6") (pinfunction "GPIO2_6") (pintype "bidirectional+no_connect"))
    )
    (net (code "60") (name "unconnected-(U5-GPIO8-Pad14)") (class "Default")
      (node (ref "U5") (pin "14") (pinfunction "GPIO8_14") (pintype "bidirectional+no_connect"))
    )
    (net (code "61") (name "unconnected-(U5-SPICLK-Pad22)") (class "Default")
      (node (ref "U5") (pin "22") (pinfunction "SPICLK_22") (pintype "bidirectional+no_connect"))
    )
    (net (code "62") (name "unconnected-(U5-SPICS0-Pad21)") (class "Default")
      (node (ref "U5") (pin "21") (pinfunction "SPICS0_21") (pintype "bidirectional+no_connect"))
    )
    (net (code "63") (name "unconnected-(U5-SPID-Pad23)") (class "Default")
      (node (ref "U5") (pin "23") (pinfunction "SPID_23") (pintype "bidirectional+no_connect"))
    )
    (net (code "64") (name "unconnected-(U5-SPIHD-Pad19)") (class "Default")
      (node (ref "U5") (pin "19") (pinfunction "SPIHD_19") (pintype "bidirectional+no_connect"))
    )
    (net (code "65") (name "unconnected-(U5-SPIQ-Pad24)") (class "Default")
      (node (ref "U5") (pin "24") (pinfunction "SPIQ_24") (pintype "bidirectional+no_connect"))
    )
    (net (code "66") (name "unconnected-(U5-SPIWP-Pad20)") (class "Default")
      (node (ref "U5") (pin "20") (pinfunction "SPIWP_20") (pintype "bidirectional+no_connect"))
    )
  )
)
